# board.net
KiCad netlist of a schematic drawn in EAGLE
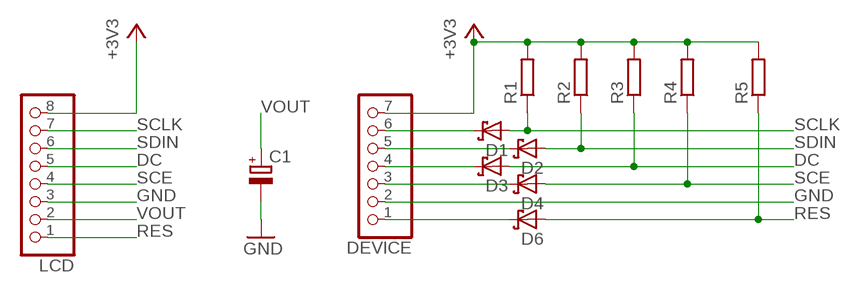
[diagram p0: schematic, sheet 1]

(export (version "E")
  (design (tool "Eeschema 10.0.6"))
  (components
    (comp (ref "C1")
      (value "CPOL-EUE2.5-5")
      (footprint "eagle-import:E2,5-5")
      (libsource (lib "eagle-import") (part "CPOL-EUE2.5-5"))
    )
    (comp (ref "D1")
      (value "SCHOTTKY-DIODESMD")
      (footprint "eagle-import:SMB")
      (libsource (lib "eagle-import") (part "SCHOTTKY-DIODESMD"))
    )
    (comp (ref "D2")
      (value "SCHOTTKY-DIODESMD")
      (footprint "eagle-import:SMB")
      (libsource (lib "eagle-import") (part "SCHOTTKY-DIODESMD"))
    )
    (comp (ref "D3")
      (value "SCHOTTKY-DIODESMD")
      (footprint "eagle-import:SMB")
      (libsource (lib "eagle-import") (part "SCHOTTKY-DIODESMD"))
    )
    (comp (ref "D4")
      (value "SCHOTTKY-DIODESMD")
      (footprint "eagle-import:SMB")
      (libsource (lib "eagle-import") (part "SCHOTTKY-DIODESMD"))
    )
    (comp (ref "D6")
      (value "SCHOTTKY-DIODESMD")
      (footprint "eagle-import:SMB")
      (libsource (lib "eagle-import") (part "SCHOTTKY-DIODESMD"))
    )
    (comp (ref "DEVICE")
      (value "PINHD-1X7")
      (footprint "eagle-import:1X07")
      (libsource (lib "eagle-import") (part "PINHD-1X7"))
    )
    (comp (ref "LCD")
      (value "PINHD-1X8")
      (footprint "eagle-import:1X08")
      (libsource (lib "eagle-import") (part "PINHD-1X8"))
    )
    (comp (ref "R1")
      (value "R-EU_R0805")
      (footprint "eagle-import:R0805")
      (libsource (lib "eagle-import") (part "R-EU_R0805"))
    )
    (comp (ref "R2")
      (value "R-EU_R0805")
      (footprint "eagle-import:R0805")
      (libsource (lib "eagle-import") (part "R-EU_R0805"))
    )
    (comp (ref "R3")
      (value "R-EU_R0805")
      (footprint "eagle-import:R0805")
      (libsource (lib "eagle-import") (part "R-EU_R0805"))
    )
    (comp (ref "R4")
      (value "R-EU_R0805")
      (footprint "eagle-import:R0805")
      (libsource (lib "eagle-import") (part "R-EU_R0805"))
    )
    (comp (ref "R5")
      (value "R-EU_R0805")
      (footprint "eagle-import:R0805")
      (libsource (lib "eagle-import") (part "R-EU_R0805"))
    )
  )
  (nets
    (net (code "1") (name "+3V3") (class "Default")
      (node (ref "DEVICE") (pin "7") (pinfunction "7_7") (pintype "passive"))
      (node (ref "LCD") (pin "8") (pinfunction "8_8") (pintype "passive"))
      (node (ref "R1") (pin "2") (pinfunction "2_2") (pintype "passive"))
      (node (ref "R2") (pin "2") (pinfunction "2_2") (pintype "passive"))
      (node (ref "R3") (pin "2") (pinfunction "2_2") (pintype "passive"))
      (node (ref "R4") (pin "2") (pinfunction "2_2") (pintype "passive"))
      (node (ref "R5") (pin "2") (pinfunction "2_2") (pintype "passive"))
    )
    (net (code "2") (name "/DC") (class "Default")
      (node (ref "D3") (pin "A") (pinfunction "A_A") (pintype "passive"))
      (node (ref "LCD") (pin "5") (pinfunction "5_5") (pintype "passive"))
      (node (ref "R3") (pin "1") (pinfunction "1_1") (pintype "passive"))
    )
    (net (code "3") (name "/RES") (class "Default")
      (node (ref "D6") (pin "A") (pinfunction "A_A") (pintype "passive"))
      (node (ref "LCD") (pin "1") (pinfunction "1_1") (pintype "passive"))
      (node (ref "R5") (pin "1") (pinfunction "1_1") (pintype "passive"))
    )
    (net (code "4") (name "/SCE") (class "Default")
      (node (ref "D4") (pin "A") (pinfunction "A_A") (pintype "passive"))
      (node (ref "LCD") (pin "4") (pinfunction "4_4") (pintype "passive"))
      (node (ref "R4") (pin "1") (pinfunction "1_1") (pintype "passive"))
    )
    (net (code "5") (name "/SCLK") (class "Default")
      (node (ref "D1") (pin "A") (pinfunction "A_A") (pintype "passive"))
      (node (ref "LCD") (pin "7") (pinfunction "7_7") (pintype "passive"))
      (node (ref "R1") (pin "1") (pinfunction "1_1") (pintype "passive"))
    )
    (net (code "6") (name "/SDIN") (class "Default")
      (node (ref "D2") (pin "A") (pinfunction "A_A") (pintype "passive"))
      (node (ref "LCD") (pin "6") (pinfunction "6_6") (pintype "passive"))
      (node (ref "R2") (pin "1") (pinfunction "1_1") (pintype "passive"))
    )
    (net (code "7") (name "/VOUT") (class "Default")
      (node (ref "C1") (pin "+") (pinfunction "+_+") (pintype "passive"))
      (node (ref "LCD") (pin "2") (pinfunction "2_2") (pintype "passive"))
    )
    (net (code "8") (name "GND") (class "Default")
      (node (ref "C1") (pin "-") (pinfunction "-_-") (pintype "passive"))
      (node (ref "DEVICE") (pin "2") (pinfunction "2_2") (pintype "passive"))
      (node (ref "LCD") (pin "3") (pinfunction "3_3") (pintype "passive"))
    )
    (net (code "9") (name "Net-(D1-PadC)") (class "Default")
      (node (ref "D1") (pin "C") (pinfunction "C_C") (pintype "passive"))
      (node (ref "DEVICE") (pin "6") (pinfunction "6_6") (pintype "passive"))
    )
    (net (code "10") (name "Net-(D2-PadC)") (class "Default")
      (node (ref "D2") (pin "C") (pinfunction "C_C") (pintype "passive"))
      (node (ref "DEVICE") (pin "5") (pinfunction "5_5") (pintype "passive"))
    )
    (net (code "11") (name "Net-(D3-PadC)") (class "Default")
      (node (ref "D3") (pin "C") (pinfunction "C_C") (pintype "passive"))
      (node (ref "DEVICE") (pin "4") (pinfunction "4_4") (pintype "passive"))
    )
    (net (code "12") (name "Net-(D4-PadC)") (class "Default")
      (node (ref "D4") (pin "C") (pinfunction "C_C") (pintype "passive"))
      (node (ref "DEVICE") (pin "3") (pinfunction "3_3") (pintype "passive"))
    )
    (net (code "13") (name "Net-(D6-PadC)") (class "Default")
      (node (ref "D6") (pin "C") (pinfunction "C_C") (pintype "passive"))
      (node (ref "DEVICE") (pin "1") (pinfunction "1_1") (pintype "passive"))
    )
  )
)
